# E17-15-CONN.net
KiCad netlist of a schematic drawn in Altium Designer
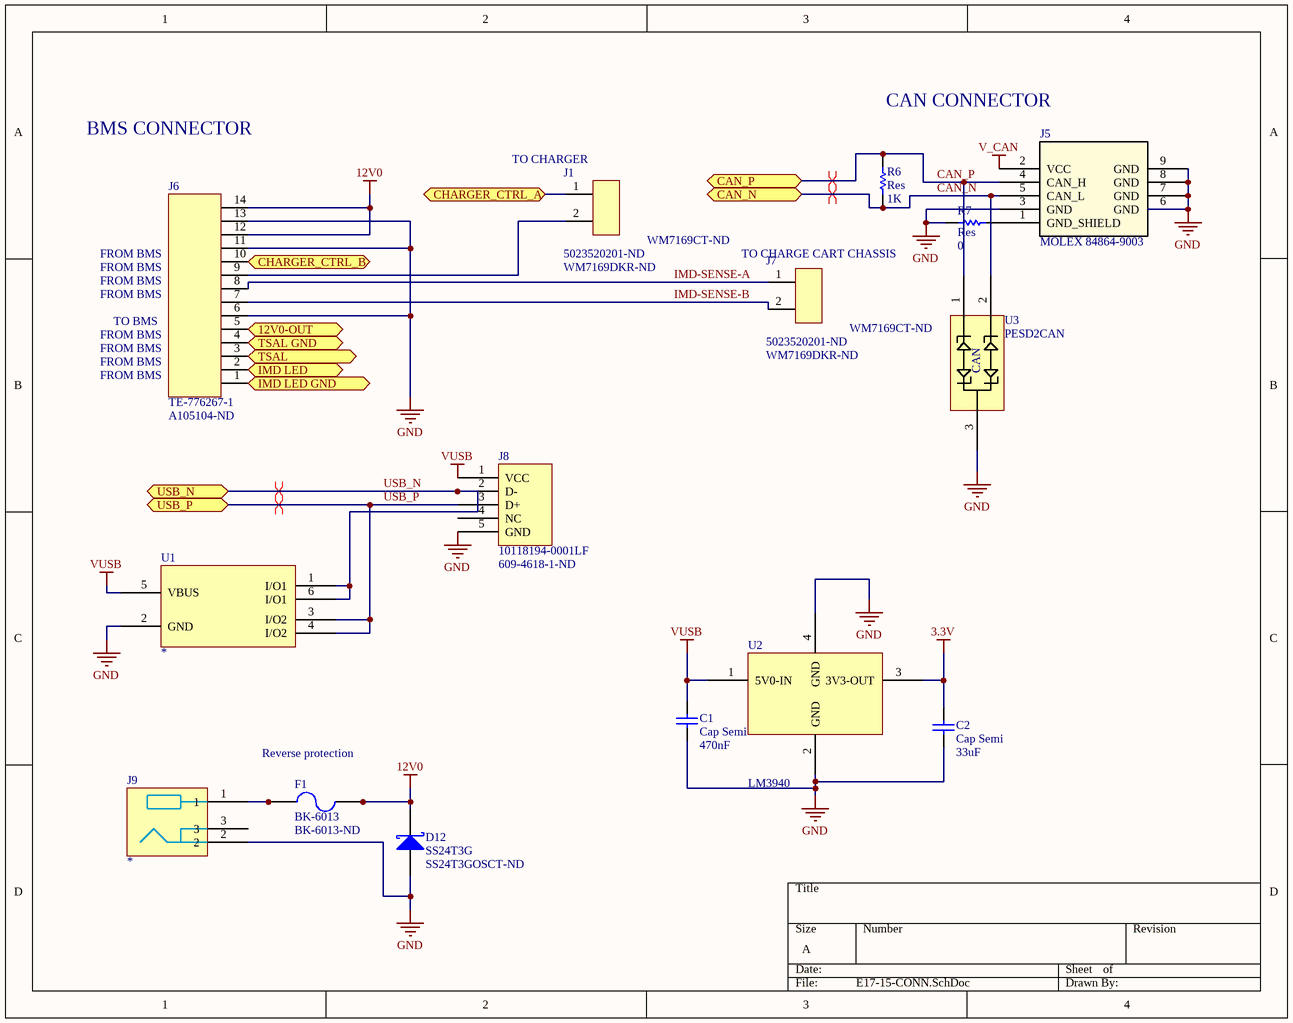
[diagram p0: E17-15-CONN.SchDoc]

(export (version "E")
  (design (tool "Eeschema 10.0.6"))
  (components
    (comp (ref "C1")
      (value "Cap Semi")
      (footprint "C1206")
      (description "Capacitor (Semiconductor SIM Model)")
      (fields (field (name "ALTIUM_VALUE") "470nF") (field (name "PUBLISHER") "Altium Limited"))
      (libsource (lib "Miscellaneous Devices") (part "Cap Semi"))
    )
    (comp (ref "C2")
      (value "Cap Semi")
      (footprint "C1206")
      (description "Capacitor (Semiconductor SIM Model)")
      (fields (field (name "ALTIUM_VALUE") "33uF") (field (name "PUBLISHER") "Altium Limited"))
      (libsource (lib "Miscellaneous Devices") (part "Cap Semi"))
    )
    (comp (ref "D12")
      (value "SS24T3G")
      (footprint "DO-214-AA")
      (description "Schottky Diode")
      (fields
        (field (name "SUPPLIER PART NUMBER 1") "SS24T3GOSCT-ND")
        (field (name "PUBLISHER") "Altium Limited")
      )
      (libsource (lib "Diodes") (part "SS24T3G"))
    )
    (comp (ref "F1")
      (value "BK-6013")
      (footprint "BK-6013")
      (description "FUSE HOLDER BLADE PCB")
      (fields (field (name "SUPPLIER PART NUMBER 1") "BK-6013-ND"))
      (libsource (lib "Fuses") (part "BK-6013"))
    )
    (comp (ref "J1")
      (value "J_5023520200")
      (footprint "MOLEX_DURACLIK_2")
      (description "MOLEX DURACLIK 2-PIN RA")
      (fields
        (field (name "SUPPLIER PART NUMBER 1") "5023520201-ND")
        (field (name "SUPPLIER PART NUMBER 2") "WM7169DKR-ND")
      )
      (libsource (lib "Molex_DuraClik") (part "J_5023520200"))
    )
    (comp (ref "J5")
      (value "MOLEX 84864-9003")
      (footprint "MOLEX 84864-9003")
      (description "CAN Micro-Change M12, Right Angle, Male")
      (libsource (lib "Connectors and Headers") (part "MOLEX 84864-9003"))
    )
    (comp (ref "J6")
      (value "TE-776267-1")
      (footprint "TE-776267-1")
      (description "CONN HEADER 14POS R/A TIN BLK")
      (fields (field (name "SUPPLIER PART NUMBER 1") "A105104-ND"))
      (libsource (lib "Connectors and Headers") (part "TE-776267-1"))
    )
    (comp (ref "J7")
      (value "J_5023520200")
      (footprint "MOLEX_DURACLIK_2")
      (description "MOLEX DURACLIK 2-PIN RA")
      (fields
        (field (name "SUPPLIER PART NUMBER 1") "5023520201-ND")
        (field (name "SUPPLIER PART NUMBER 2") "WM7169DKR-ND")
      )
      (libsource (lib "Molex_DuraClik") (part "J_5023520200"))
    )
    (comp (ref "J8")
      (value "10118194-0001LF")
      (footprint "10118194-0001LF")
      (description "CONN USB MICRO B RECPT SMT R/A")
      (fields (field (name "SUPPLIER PART NUMBER 1") "609-4618-1-ND"))
      (libsource (lib "Connectors and Headers") (part "10118194-0001LF"))
    )
    (comp (ref "J9")
      (value "*")
      (footprint "EJ805A")
      (description "CONN PWR JACK 2.1X5.5MM SOLDER")
      (libsource (lib "E17-12_CC") (part "EJ508A"))
    )
    (comp (ref "R6")
      (value "Res")
      (footprint "2012[0805]")
      (description "Surface Mount Resistor")
      (fields (field (name "ALTIUM_VALUE") "1K") (field (name "PUBLISHER") "Altium Limited"))
      (libsource (lib "Resistors") (part "Res"))
    )
    (comp (ref "R7")
      (value "Res")
      (footprint "2012[0805]")
      (description "Surface Mount Resistor")
      (fields (field (name "ALTIUM_VALUE") "0") (field (name "PUBLISHER") "Altium Limited"))
      (libsource (lib "Resistors") (part "Res"))
    )
    (comp (ref "U1") (value "*") (footprint "SOP6") (libsource (lib "E17-12_CC") (part "USBL6-2")))
    (comp (ref "U2") (value "LM3940") (footprint "TO-263-3") (libsource (lib "E17-12_CC") (part "LM3940")))
    (comp (ref "U3")
      (value "PESD2CAN")
      (footprint "SOT95P230X110-3N")
      (libsource (lib "E17-12_CC") (part "PESD2CAN"))
    )
  )
  (nets
    (net (code "1") (name "/12V0-OUT") (class "Default") (node (ref "J6") (pin "5") (pintype "passive")))
    (net (code "2") (name "/CAN_N") (class "Default")
      (node (ref "J5") (pin "5") (pinfunction "CAN_L_5") (pintype "passive"))
      (node (ref "R6") (pin "1") (pinfunction "1_1") (pintype "passive"))
      (node (ref "U3") (pin "2") (pinfunction "CATH2_2") (pintype "passive"))
    )
    (net (code "3") (name "/CAN_P") (class "Default")
      (node (ref "J5") (pin "4") (pinfunction "CAN_H_4") (pintype "passive"))
      (node (ref "R6") (pin "2") (pinfunction "2_2") (pintype "passive"))
      (node (ref "U3") (pin "1") (pinfunction "CATH1_1") (pintype "passive"))
    )
    (net (code "4") (name "/CHARGER_CTRL_A") (class "Default")
      (node (ref "J1") (pin "1") (pinfunction "1_1") (pintype "passive"))
    )
    (net (code "5") (name "/CHARGER_CTRL_B") (class "Default")
      (node (ref "J6") (pin "10") (pintype "passive"))
    )
    (net (code "6") (name "/IMD LED") (class "Default") (node (ref "J6") (pin "2") (pintype "passive")))
    (net (code "7") (name "/IMD LED GND") (class "Default") (node (ref "J6") (pin "1") (pintype "passive")))
    (net (code "8") (name "/IMD-SENSE-A") (class "Default")
      (node (ref "J6") (pin "8") (pintype "passive"))
      (node (ref "J7") (pin "1") (pinfunction "1_1") (pintype "passive"))
    )
    (net (code "9") (name "/IMD-SENSE-B") (class "Default")
      (node (ref "J6") (pin "7") (pintype "passive"))
      (node (ref "J7") (pin "2") (pinfunction "2_2") (pintype "passive"))
    )
    (net (code "10") (name "/TSAL") (class "Default") (node (ref "J6") (pin "3") (pintype "passive")))
    (net (code "11") (name "/TSAL GND") (class "Default") (node (ref "J6") (pin "4") (pintype "passive")))
    (net (code "12") (name "/USB_N") (class "Default")
      (node (ref "J8") (pin "2") (pinfunction "D-_2") (pintype "passive"))
      (node (ref "U1") (pin "1") (pinfunction "I/O1_1") (pintype "passive"))
      (node (ref "U1") (pin "6") (pinfunction "I/O1_6") (pintype "passive"))
    )
    (net (code "13") (name "/USB_P") (class "Default")
      (node (ref "J8") (pin "3") (pinfunction "D+_3") (pintype "passive"))
      (node (ref "U1") (pin "3") (pinfunction "I/O2_3") (pintype "passive"))
      (node (ref "U1") (pin "4") (pinfunction "I/O2_4") (pintype "passive"))
    )
    (net (code "14") (name "3.3V") (class "Default")
      (node (ref "C2") (pin "2") (pinfunction "2_2") (pintype "passive"))
      (node (ref "U2") (pin "3") (pinfunction "3V3-OUT_3") (pintype "passive"))
    )
    (net (code "15") (name "12V0") (class "Default")
      (node (ref "D12") (pin "2") (pinfunction "K_2") (pintype "passive"))
      (node (ref "F1") (pin "3") (pinfunction "3_3") (pintype "passive"))
      (node (ref "F1") (pin "4") (pinfunction "4_4") (pintype "passive"))
      (node (ref "J6") (pin "12") (pintype "passive"))
      (node (ref "J6") (pin "14") (pintype "passive"))
    )
    (net (code "16") (name "GND") (class "Default")
      (node (ref "C1") (pin "1") (pinfunction "1_1") (pintype "passive"))
      (node (ref "C2") (pin "1") (pinfunction "1_1") (pintype "passive"))
      (node (ref "D12") (pin "1") (pinfunction "A_1") (pintype "passive"))
      (node (ref "J5") (pin "3") (pinfunction "GND_3") (pintype "passive"))
      (node (ref "J5") (pin "6") (pinfunction "GND_6") (pintype "passive"))
      (node (ref "J5") (pin "7") (pinfunction "GND_7") (pintype "passive"))
      (node (ref "J5") (pin "8") (pinfunction "GND_8") (pintype "passive"))
      (node (ref "J5") (pin "9") (pinfunction "GND_9") (pintype "passive"))
      (node (ref "J6") (pin "11") (pintype "passive"))
      (node (ref "J6") (pin "13") (pintype "passive"))
      (node (ref "J6") (pin "6") (pintype "passive"))
      (node (ref "J8") (pin "5") (pinfunction "GND_5") (pintype "passive"))
      (node (ref "J9") (pin "2") (pinfunction "2_2") (pintype "power_in"))
      (node (ref "R7") (pin "1") (pinfunction "1_1") (pintype "passive"))
      (node (ref "U1") (pin "2") (pinfunction "GND_2") (pintype "power_in"))
      (node (ref "U2") (pin "2") (pinfunction "GND_2") (pintype "passive"))
      (node (ref "U2") (pin "4") (pinfunction "GND_4") (pintype "passive"))
      (node (ref "U3") (pin "3") (pinfunction "COM_3") (pintype "passive"))
    )
    (net (code "17") (name "Net-(F1-Pad1)") (class "Default")
      (node (ref "F1") (pin "1") (pinfunction "1_1") (pintype "passive"))
      (node (ref "F1") (pin "2") (pinfunction "2_2") (pintype "passive"))
      (node (ref "J9") (pin "1") (pinfunction "1_1") (pintype "power_in"))
    )
    (net (code "18") (name "Net-(J1-Pad2)") (class "Default")
      (node (ref "J1") (pin "2") (pinfunction "2_2") (pintype "passive"))
      (node (ref "J6") (pin "9") (pintype "passive"))
    )
    (net (code "19") (name "Net-(J5-GND_SHIELD)") (class "Default")
      (node (ref "J5") (pin "1") (pinfunction "GND_SHIELD_1") (pintype "passive"))
      (node (ref "R7") (pin "2") (pinfunction "2_2") (pintype "passive"))
    )
    (net (code "20") (name "VUSB") (class "Default")
      (node (ref "C1") (pin "2") (pinfunction "2_2") (pintype "passive"))
      (node (ref "J8") (pin "1") (pinfunction "VCC_1") (pintype "passive"))
      (node (ref "U1") (pin "5") (pinfunction "VBUS_5") (pintype "power_in"))
      (node (ref "U2") (pin "1") (pinfunction "5V0-IN_1") (pintype "passive"))
    )
    (net (code "21") (name "V_CAN") (class "Default")
      (node (ref "J5") (pin "2") (pinfunction "VCC_2") (pintype "passive"))
    )
    (net (code "22") (name "unconnected-(J8-NC-Pad4)") (class "Default")
      (node (ref "J8") (pin "4") (pinfunction "NC_4") (pintype "passive"))
    )
    (net (code "23") (name "unconnected-(J9-Pad3)") (class "Default")
      (node (ref "J9") (pin "3") (pinfunction "3_3") (pintype "passive"))
    )
  )
)
